# sample_holder.net
KiCad netlist of a schematic drawn in EAGLE
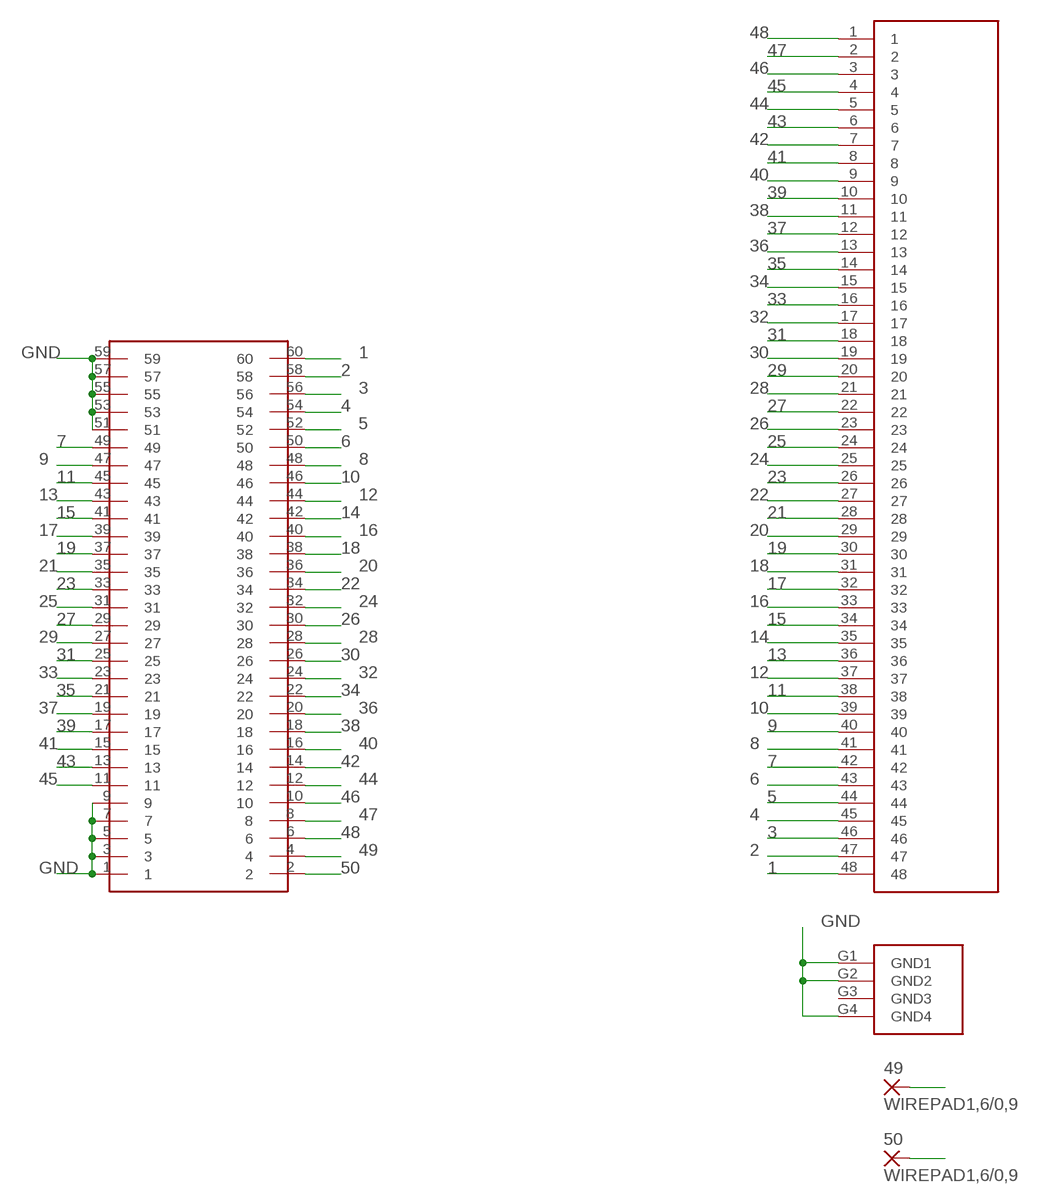
[diagram p0: schematic, sheet 1]

(export (version "E")
  (design (tool "Eeschema 10.0.6"))
  (components
    (comp (ref "49")
      (value "WIREPAD1,6/0,9")
      (footprint "eagle-import:1,6_0,9")
      (libsource (lib "eagle-import") (part "WIREPAD1,6/0,9"))
    )
    (comp (ref "50")
      (value "WIREPAD1,6/0,9")
      (footprint "eagle-import:1,6_0,9")
      (libsource (lib "eagle-import") (part "WIREPAD1,6/0,9"))
    )
    (comp (ref "U$1")
      (value "MEC5-030-CARD-ALL")
      (footprint "eagle-import:MEC-030-CARD-ALL")
      (libsource (lib "eagle-import") (part "MEC5-030-CARD-ALL"))
    )
    (comp (ref "U$2")
      (value "FOLKLAB-48PADS")
      (footprint "eagle-import:FOLKLAB-48PADS")
      (libsource (lib "eagle-import") (part "FOLKLAB-48PADS"))
    )
  )
  (nets
    (net (code "1") (name "/1") (class "Default")
      (node (ref "U$1") (pin "60") (pinfunction "60_60") (pintype "bidirectional"))
      (node (ref "U$2") (pin "48") (pinfunction "48_48") (pintype "bidirectional"))
    )
    (net (code "2") (name "/2") (class "Default")
      (node (ref "U$1") (pin "58") (pinfunction "58_58") (pintype "bidirectional"))
      (node (ref "U$2") (pin "47") (pinfunction "47_47") (pintype "bidirectional"))
    )
    (net (code "3") (name "/3") (class "Default")
      (node (ref "U$1") (pin "56") (pinfunction "56_56") (pintype "bidirectional"))
      (node (ref "U$2") (pin "46") (pinfunction "46_46") (pintype "bidirectional"))
    )
    (net (code "4") (name "/4") (class "Default")
      (node (ref "U$1") (pin "54") (pinfunction "54_54") (pintype "bidirectional"))
      (node (ref "U$2") (pin "45") (pinfunction "45_45") (pintype "bidirectional"))
    )
    (net (code "5") (name "/5") (class "Default")
      (node (ref "U$1") (pin "52") (pinfunction "52_52") (pintype "bidirectional"))
      (node (ref "U$2") (pin "44") (pinfunction "44_44") (pintype "bidirectional"))
    )
    (net (code "6") (name "/6") (class "Default")
      (node (ref "U$1") (pin "50") (pinfunction "50_50") (pintype "bidirectional"))
      (node (ref "U$2") (pin "43") (pinfunction "43_43") (pintype "bidirectional"))
    )
    (net (code "7") (name "/7") (class "Default")
      (node (ref "U$1") (pin "49") (pinfunction "49_49") (pintype "bidirectional"))
      (node (ref "U$2") (pin "42") (pinfunction "42_42") (pintype "bidirectional"))
    )
    (net (code "8") (name "/8") (class "Default")
      (node (ref "U$1") (pin "48") (pinfunction "48_48") (pintype "bidirectional"))
      (node (ref "U$2") (pin "41") (pinfunction "41_41") (pintype "bidirectional"))
    )
    (net (code "9") (name "/9") (class "Default")
      (node (ref "U$1") (pin "47") (pinfunction "47_47") (pintype "bidirectional"))
      (node (ref "U$2") (pin "40") (pinfunction "40_40") (pintype "bidirectional"))
    )
    (net (code "10") (name "/10") (class "Default")
      (node (ref "U$1") (pin "46") (pinfunction "46_46") (pintype "bidirectional"))
      (node (ref "U$2") (pin "39") (pinfunction "39_39") (pintype "bidirectional"))
    )
    (net (code "11") (name "/11") (class "Default")
      (node (ref "U$1") (pin "45") (pinfunction "45_45") (pintype "bidirectional"))
      (node (ref "U$2") (pin "38") (pinfunction "38_38") (pintype "bidirectional"))
    )
    (net (code "12") (name "/12") (class "Default")
      (node (ref "U$1") (pin "44") (pinfunction "44_44") (pintype "bidirectional"))
      (node (ref "U$2") (pin "37") (pinfunction "37_37") (pintype "bidirectional"))
    )
    (net (code "13") (name "/13") (class "Default")
      (node (ref "U$1") (pin "43") (pinfunction "43_43") (pintype "bidirectional"))
      (node (ref "U$2") (pin "36") (pinfunction "36_36") (pintype "bidirectional"))
    )
    (net (code "14") (name "/14") (class "Default")
      (node (ref "U$1") (pin "42") (pinfunction "42_42") (pintype "bidirectional"))
      (node (ref "U$2") (pin "35") (pinfunction "35_35") (pintype "bidirectional"))
    )
    (net (code "15") (name "/15") (class "Default")
      (node (ref "U$1") (pin "41") (pinfunction "41_41") (pintype "bidirectional"))
      (node (ref "U$2") (pin "34") (pinfunction "34_34") (pintype "bidirectional"))
    )
    (net (code "16") (name "/16") (class "Default")
      (node (ref "U$1") (pin "40") (pinfunction "40_40") (pintype "bidirectional"))
      (node (ref "U$2") (pin "33") (pinfunction "33_33") (pintype "bidirectional"))
    )
    (net (code "17") (name "/17") (class "Default")
      (node (ref "U$1") (pin "39") (pinfunction "39_39") (pintype "bidirectional"))
      (node (ref "U$2") (pin "32") (pinfunction "32_32") (pintype "bidirectional"))
    )
    (net (code "18") (name "/18") (class "Default")
      (node (ref "U$1") (pin "38") (pinfunction "38_38") (pintype "bidirectional"))
      (node (ref "U$2") (pin "31") (pinfunction "31_31") (pintype "bidirectional"))
    )
    (net (code "19") (name "/19") (class "Default")
      (node (ref "U$1") (pin "37") (pinfunction "37_37") (pintype "bidirectional"))
      (node (ref "U$2") (pin "30") (pinfunction "30_30") (pintype "bidirectional"))
    )
    (net (code "20") (name "/20") (class "Default")
      (node (ref "U$1") (pin "36") (pinfunction "36_36") (pintype "bidirectional"))
      (node (ref "U$2") (pin "29") (pinfunction "29_29") (pintype "bidirectional"))
    )
    (net (code "21") (name "/21") (class "Default")
      (node (ref "U$1") (pin "35") (pinfunction "35_35") (pintype "bidirectional"))
      (node (ref "U$2") (pin "28") (pinfunction "28_28") (pintype "bidirectional"))
    )
    (net (code "22") (name "/22") (class "Default")
      (node (ref "U$1") (pin "34") (pinfunction "34_34") (pintype "bidirectional"))
      (node (ref "U$2") (pin "27") (pinfunction "27_27") (pintype "bidirectional"))
    )
    (net (code "23") (name "/23") (class "Default")
      (node (ref "U$1") (pin "33") (pinfunction "33_33") (pintype "bidirectional"))
      (node (ref "U$2") (pin "26") (pinfunction "26_26") (pintype "bidirectional"))
    )
    (net (code "24") (name "/24") (class "Default")
      (node (ref "U$1") (pin "32") (pinfunction "32_32") (pintype "bidirectional"))
      (node (ref "U$2") (pin "25") (pinfunction "25_25") (pintype "bidirectional"))
    )
    (net (code "25") (name "/25") (class "Default")
      (node (ref "U$1") (pin "31") (pinfunction "31_31") (pintype "bidirectional"))
      (node (ref "U$2") (pin "24") (pinfunction "24_24") (pintype "bidirectional"))
    )
    (net (code "26") (name "/26") (class "Default")
      (node (ref "U$1") (pin "30") (pinfunction "30_30") (pintype "bidirectional"))
      (node (ref "U$2") (pin "23") (pinfunction "23_23") (pintype "bidirectional"))
    )
    (net (code "27") (name "/27") (class "Default")
      (node (ref "U$1") (pin "29") (pinfunction "29_29") (pintype "bidirectional"))
      (node (ref "U$2") (pin "22") (pinfunction "22_22") (pintype "bidirectional"))
    )
    (net (code "28") (name "/28") (class "Default")
      (node (ref "U$1") (pin "28") (pinfunction "28_28") (pintype "bidirectional"))
      (node (ref "U$2") (pin "21") (pinfunction "21_21") (pintype "bidirectional"))
    )
    (net (code "29") (name "/29") (class "Default")
      (node (ref "U$1") (pin "27") (pinfunction "27_27") (pintype "bidirectional"))
      (node (ref "U$2") (pin "20") (pinfunction "20_20") (pintype "bidirectional"))
    )
    (net (code "30") (name "/30") (class "Default")
      (node (ref "U$1") (pin "26") (pinfunction "26_26") (pintype "bidirectional"))
      (node (ref "U$2") (pin "19") (pinfunction "19_19") (pintype "bidirectional"))
    )
    (net (code "31") (name "/31") (class "Default")
      (node (ref "U$1") (pin "25") (pinfunction "25_25") (pintype "bidirectional"))
      (node (ref "U$2") (pin "18") (pinfunction "18_18") (pintype "bidirectional"))
    )
    (net (code "32") (name "/32") (class "Default")
      (node (ref "U$1") (pin "24") (pinfunction "24_24") (pintype "bidirectional"))
      (node (ref "U$2") (pin "17") (pinfunction "17_17") (pintype "bidirectional"))
    )
    (net (code "33") (name "/33") (class "Default")
      (node (ref "U$1") (pin "23") (pinfunction "23_23") (pintype "bidirectional"))
      (node (ref "U$2") (pin "16") (pinfunction "16_16") (pintype "bidirectional"))
    )
    (net (code "34") (name "/34") (class "Default")
      (node (ref "U$1") (pin "22") (pinfunction "22_22") (pintype "bidirectional"))
      (node (ref "U$2") (pin "15") (pinfunction "15_15") (pintype "bidirectional"))
    )
    (net (code "35") (name "/35") (class "Default")
      (node (ref "U$1") (pin "21") (pinfunction "21_21") (pintype "bidirectional"))
      (node (ref "U$2") (pin "14") (pinfunction "14_14") (pintype "bidirectional"))
    )
    (net (code "36") (name "/36") (class "Default")
      (node (ref "U$1") (pin "20") (pinfunction "20_20") (pintype "bidirectional"))
      (node (ref "U$2") (pin "13") (pinfunction "13_13") (pintype "bidirectional"))
    )
    (net (code "37") (name "/37") (class "Default")
      (node (ref "U$1") (pin "19") (pinfunction "19_19") (pintype "bidirectional"))
      (node (ref "U$2") (pin "12") (pinfunction "12_12") (pintype "bidirectional"))
    )
    (net (code "38") (name "/38") (class "Default")
      (node (ref "U$1") (pin "18") (pinfunction "18_18") (pintype "bidirectional"))
      (node (ref "U$2") (pin "11") (pinfunction "11_11") (pintype "bidirectional"))
    )
    (net (code "39") (name "/39") (class "Default")
      (node (ref "U$1") (pin "17") (pinfunction "17_17") (pintype "bidirectional"))
      (node (ref "U$2") (pin "10") (pinfunction "10_10") (pintype "bidirectional"))
    )
    (net (code "40") (name "/40") (class "Default")
      (node (ref "U$1") (pin "16") (pinfunction "16_16") (pintype "bidirectional"))
      (node (ref "U$2") (pin "9") (pinfunction "9_9") (pintype "bidirectional"))
    )
    (net (code "41") (name "/41") (class "Default")
      (node (ref "U$1") (pin "15") (pinfunction "15_15") (pintype "bidirectional"))
      (node (ref "U$2") (pin "8") (pinfunction "8_8") (pintype "bidirectional"))
    )
    (net (code "42") (name "/42") (class "Default")
      (node (ref "U$1") (pin "14") (pinfunction "14_14") (pintype "bidirectional"))
      (node (ref "U$2") (pin "7") (pinfunction "7_7") (pintype "bidirectional"))
    )
    (net (code "43") (name "/43") (class "Default")
      (node (ref "U$1") (pin "13") (pinfunction "13_13") (pintype "bidirectional"))
      (node (ref "U$2") (pin "6") (pinfunction "6_6") (pintype "bidirectional"))
    )
    (net (code "44") (name "/44") (class "Default")
      (node (ref "U$1") (pin "12") (pinfunction "12_12") (pintype "bidirectional"))
      (node (ref "U$2") (pin "5") (pinfunction "5_5") (pintype "bidirectional"))
    )
    (net (code "45") (name "/45") (class "Default")
      (node (ref "U$1") (pin "11") (pinfunction "11_11") (pintype "bidirectional"))
      (node (ref "U$2") (pin "4") (pinfunction "4_4") (pintype "bidirectional"))
    )
    (net (code "46") (name "/46") (class "Default")
      (node (ref "U$1") (pin "10") (pinfunction "10_10") (pintype "bidirectional"))
      (node (ref "U$2") (pin "3") (pinfunction "3_3") (pintype "bidirectional"))
    )
    (net (code "47") (name "/47") (class "Default")
      (node (ref "U$1") (pin "8") (pinfunction "8_8") (pintype "bidirectional"))
      (node (ref "U$2") (pin "2") (pinfunction "2_2") (pintype "bidirectional"))
    )
    (net (code "48") (name "/48") (class "Default")
      (node (ref "U$1") (pin "6") (pinfunction "6_6") (pintype "bidirectional"))
      (node (ref "U$2") (pin "1") (pinfunction "1_1") (pintype "bidirectional"))
    )
    (net (code "49") (name "/49") (class "Default")
      (node (ref "49") (pin "1") (pinfunction "P_1") (pintype "passive"))
      (node (ref "U$1") (pin "4") (pinfunction "4_4") (pintype "bidirectional"))
    )
    (net (code "50") (name "/50") (class "Default")
      (node (ref "50") (pin "1") (pinfunction "P_1") (pintype "passive"))
      (node (ref "U$1") (pin "2") (pinfunction "2_2") (pintype "bidirectional"))
    )
    (net (code "51") (name "/GND") (class "Default")
      (node (ref "U$1") (pin "1") (pinfunction "1_1") (pintype "bidirectional"))
      (node (ref "U$1") (pin "3") (pinfunction "3_3") (pintype "bidirectional"))
      (node (ref "U$1") (pin "5") (pinfunction "5_5") (pintype "bidirectional"))
      (node (ref "U$1") (pin "51") (pinfunction "51_51") (pintype "bidirectional"))
      (node (ref "U$1") (pin "53") (pinfunction "53_53") (pintype "bidirectional"))
      (node (ref "U$1") (pin "55") (pinfunction "55_55") (pintype "bidirectional"))
      (node (ref "U$1") (pin "57") (pinfunction "57_57") (pintype "bidirectional"))
      (node (ref "U$1") (pin "59") (pinfunction "59_59") (pintype "bidirectional"))
      (node (ref "U$1") (pin "7") (pinfunction "7_7") (pintype "bidirectional"))
      (node (ref "U$1") (pin "9") (pinfunction "9_9") (pintype "bidirectional"))
      (node (ref "U$2") (pin "G1") (pinfunction "GND1_G1") (pintype "bidirectional"))
      (node (ref "U$2") (pin "G2") (pinfunction "GND2_G2") (pintype "bidirectional"))
      (node (ref "U$2") (pin "G4") (pinfunction "GND4_G4") (pintype "bidirectional"))
    )
    (net (code "52") (name "unconnected-(U$2B-GND3-PadG3)") (class "Default")
      (node (ref "U$2") (pin "G3") (pinfunction "GND3_G3") (pintype "bidirectional"))
    )
  )
)
